# Accelerometer.net
KiCad netlist of a schematic drawn in Altium Designer
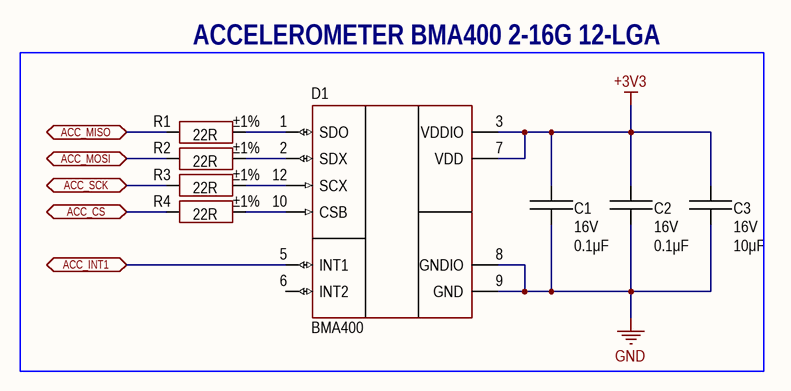
[diagram p0: Accelerometer.SchDoc]

(export (version "E")
  (design (tool "Eeschema 10.0.6"))
  (components
    (comp (ref "C1")
      (value "0.1μF")
      (footprint "CAP: 0402")
      (description "±10% 16V Ceramic Capacitor X7R 0402 (1005 Metric)")
      (fields
        (field (name "MANUFACTURER") "Yageo")
        (field (name "PARTNUMBER") "CC0402KRX7R7BB104")
        (field (name "VOLTAGE") "16V")
      )
      (libsource (lib "capacitor") (part "Ceramic_0402"))
    )
    (comp (ref "C2")
      (value "0.1μF")
      (footprint "CAP: 0402")
      (description "±10% 16V Ceramic Capacitor X7R 0402 (1005 Metric)")
      (fields
        (field (name "MANUFACTURER") "Yageo")
        (field (name "PARTNUMBER") "CC0402KRX7R7BB104")
        (field (name "VOLTAGE") "16V")
      )
      (libsource (lib "capacitor") (part "Ceramic_0402"))
    )
    (comp (ref "C3")
      (value "10μF")
      (footprint "CAP: 0805")
      (description "±20% 16V Ceramic Capacitor X7R 0805 (2012 Metric)")
      (fields
        (field (name "MANUFACTURER") "Yageo")
        (field (name "PARTNUMBER") "CC0805MKX7R7BB106")
        (field (name "VOLTAGE") "16V")
      )
      (libsource (lib "capacitor") (part "Ceramic_0805"))
    )
    (comp (ref "D1")
      (value "~")
      (footprint "12-VFLGA")
      (description "Accelerometer X, Y, Z Axis ±2g, 4g, 8g, 16g - 12-LGA (2x2)")
      (fields
        (field (name "MANUFACTURER") "Bosch Sensortec")
        (field (name "VALUEMANUFACTURERPARTNUMBER") "IC accelerometer, Digital sensor, , , , -40...+85°C, 12-VFLGA")
        (field (name "PARTNUMBER") "BMA400")
      )
      (libsource (lib "MyLib") (part "BMA400"))
    )
    (comp (ref "R1")
      (value "22R")
      (footprint "RES: 0402")
      (description "22 Ohms ±1% 0.063W, 1/16W Chip Resistor 0402 (1005 Metric) Moisture Resistant Thick Film")
      (fields
        (field (name "MANUFACTURER") "Yageo")
        (field (name "PARTNUMBER") "RC0402FR-0722RL")
        (field (name "TOLERANCE") "±1%")
      )
      (libsource (lib "resistor") (part "Resistor_0402"))
    )
    (comp (ref "R2")
      (value "22R")
      (footprint "RES: 0402")
      (description "22 Ohms ±1% 0.063W, 1/16W Chip Resistor 0402 (1005 Metric) Moisture Resistant Thick Film")
      (fields
        (field (name "MANUFACTURER") "Yageo")
        (field (name "PARTNUMBER") "RC0402FR-0722RL")
        (field (name "TOLERANCE") "±1%")
      )
      (libsource (lib "resistor") (part "Resistor_0402"))
    )
    (comp (ref "R3")
      (value "22R")
      (footprint "RES: 0402")
      (description "22 Ohms ±1% 0.063W, 1/16W Chip Resistor 0402 (1005 Metric) Moisture Resistant Thick Film")
      (fields
        (field (name "MANUFACTURER") "Yageo")
        (field (name "PARTNUMBER") "RC0402FR-0722RL")
        (field (name "TOLERANCE") "±1%")
      )
      (libsource (lib "resistor") (part "Resistor_0402"))
    )
    (comp (ref "R4")
      (value "22R")
      (footprint "RES: 0402")
      (description "22 Ohms ±1% 0.063W, 1/16W Chip Resistor 0402 (1005 Metric) Moisture Resistant Thick Film")
      (fields
        (field (name "MANUFACTURER") "Yageo")
        (field (name "PARTNUMBER") "RC0402FR-0722RL")
        (field (name "TOLERANCE") "±1%")
      )
      (libsource (lib "resistor") (part "Resistor_0402"))
    )
  )
  (nets
    (net (code "1") (name "+3V3") (class "Default")
      (node (ref "C1") (pin "2") (pinfunction "2_2") (pintype "passive"))
      (node (ref "C2") (pin "2") (pinfunction "2_2") (pintype "passive"))
      (node (ref "C3") (pin "2") (pinfunction "2_2") (pintype "passive"))
      (node (ref "D1") (pin "3") (pinfunction "VDDIO_3") (pintype "power_in"))
      (node (ref "D1") (pin "7") (pinfunction "VDD_7") (pintype "power_in"))
    )
    (net (code "2") (name "/ACC_CS") (class "Default")
      (node (ref "R4") (pin "1") (pinfunction "1_1") (pintype "passive"))
    )
    (net (code "3") (name "/ACC_INT1") (class "Default")
      (node (ref "D1") (pin "5") (pinfunction "INT1_5") (pintype "bidirectional"))
    )
    (net (code "4") (name "/ACC_MISO") (class "Default")
      (node (ref "R1") (pin "1") (pinfunction "1_1") (pintype "passive"))
    )
    (net (code "5") (name "/ACC_MOSI") (class "Default")
      (node (ref "R2") (pin "1") (pinfunction "1_1") (pintype "passive"))
    )
    (net (code "6") (name "/ACC_SCK") (class "Default")
      (node (ref "R3") (pin "1") (pinfunction "1_1") (pintype "passive"))
    )
    (net (code "7") (name "GND") (class "Default")
      (node (ref "C1") (pin "1") (pinfunction "1_1") (pintype "passive"))
      (node (ref "C2") (pin "1") (pinfunction "1_1") (pintype "passive"))
      (node (ref "C3") (pin "1") (pinfunction "1_1") (pintype "passive"))
      (node (ref "D1") (pin "8") (pinfunction "GNDIO_8") (pintype "power_in"))
      (node (ref "D1") (pin "9") (pinfunction "GND_9") (pintype "power_in"))
    )
    (net (code "8") (name "Net-(D1-CSB)") (class "Default")
      (node (ref "D1") (pin "10") (pinfunction "CSB_10") (pintype "input"))
      (node (ref "R4") (pin "2") (pinfunction "2_2") (pintype "passive"))
    )
    (net (code "9") (name "Net-(D1-SCX)") (class "Default")
      (node (ref "D1") (pin "12") (pinfunction "SCX_12") (pintype "input"))
      (node (ref "R3") (pin "2") (pinfunction "2_2") (pintype "passive"))
    )
    (net (code "10") (name "Net-(D1-SDO)") (class "Default")
      (node (ref "D1") (pin "1") (pinfunction "SDO_1") (pintype "bidirectional"))
      (node (ref "R1") (pin "2") (pinfunction "2_2") (pintype "passive"))
    )
    (net (code "11") (name "Net-(D1-SDX)") (class "Default")
      (node (ref "D1") (pin "2") (pinfunction "SDX_2") (pintype "bidirectional"))
      (node (ref "R2") (pin "2") (pinfunction "2_2") (pintype "passive"))
    )
    (net (code "12") (name "unconnected-(D1-INT2-Pad6)") (class "Default")
      (node (ref "D1") (pin "6") (pinfunction "INT2_6") (pintype "bidirectional"))
    )
  )
)
